# test-board-64.net
KiCad netlist of a schematic drawn in EAGLE
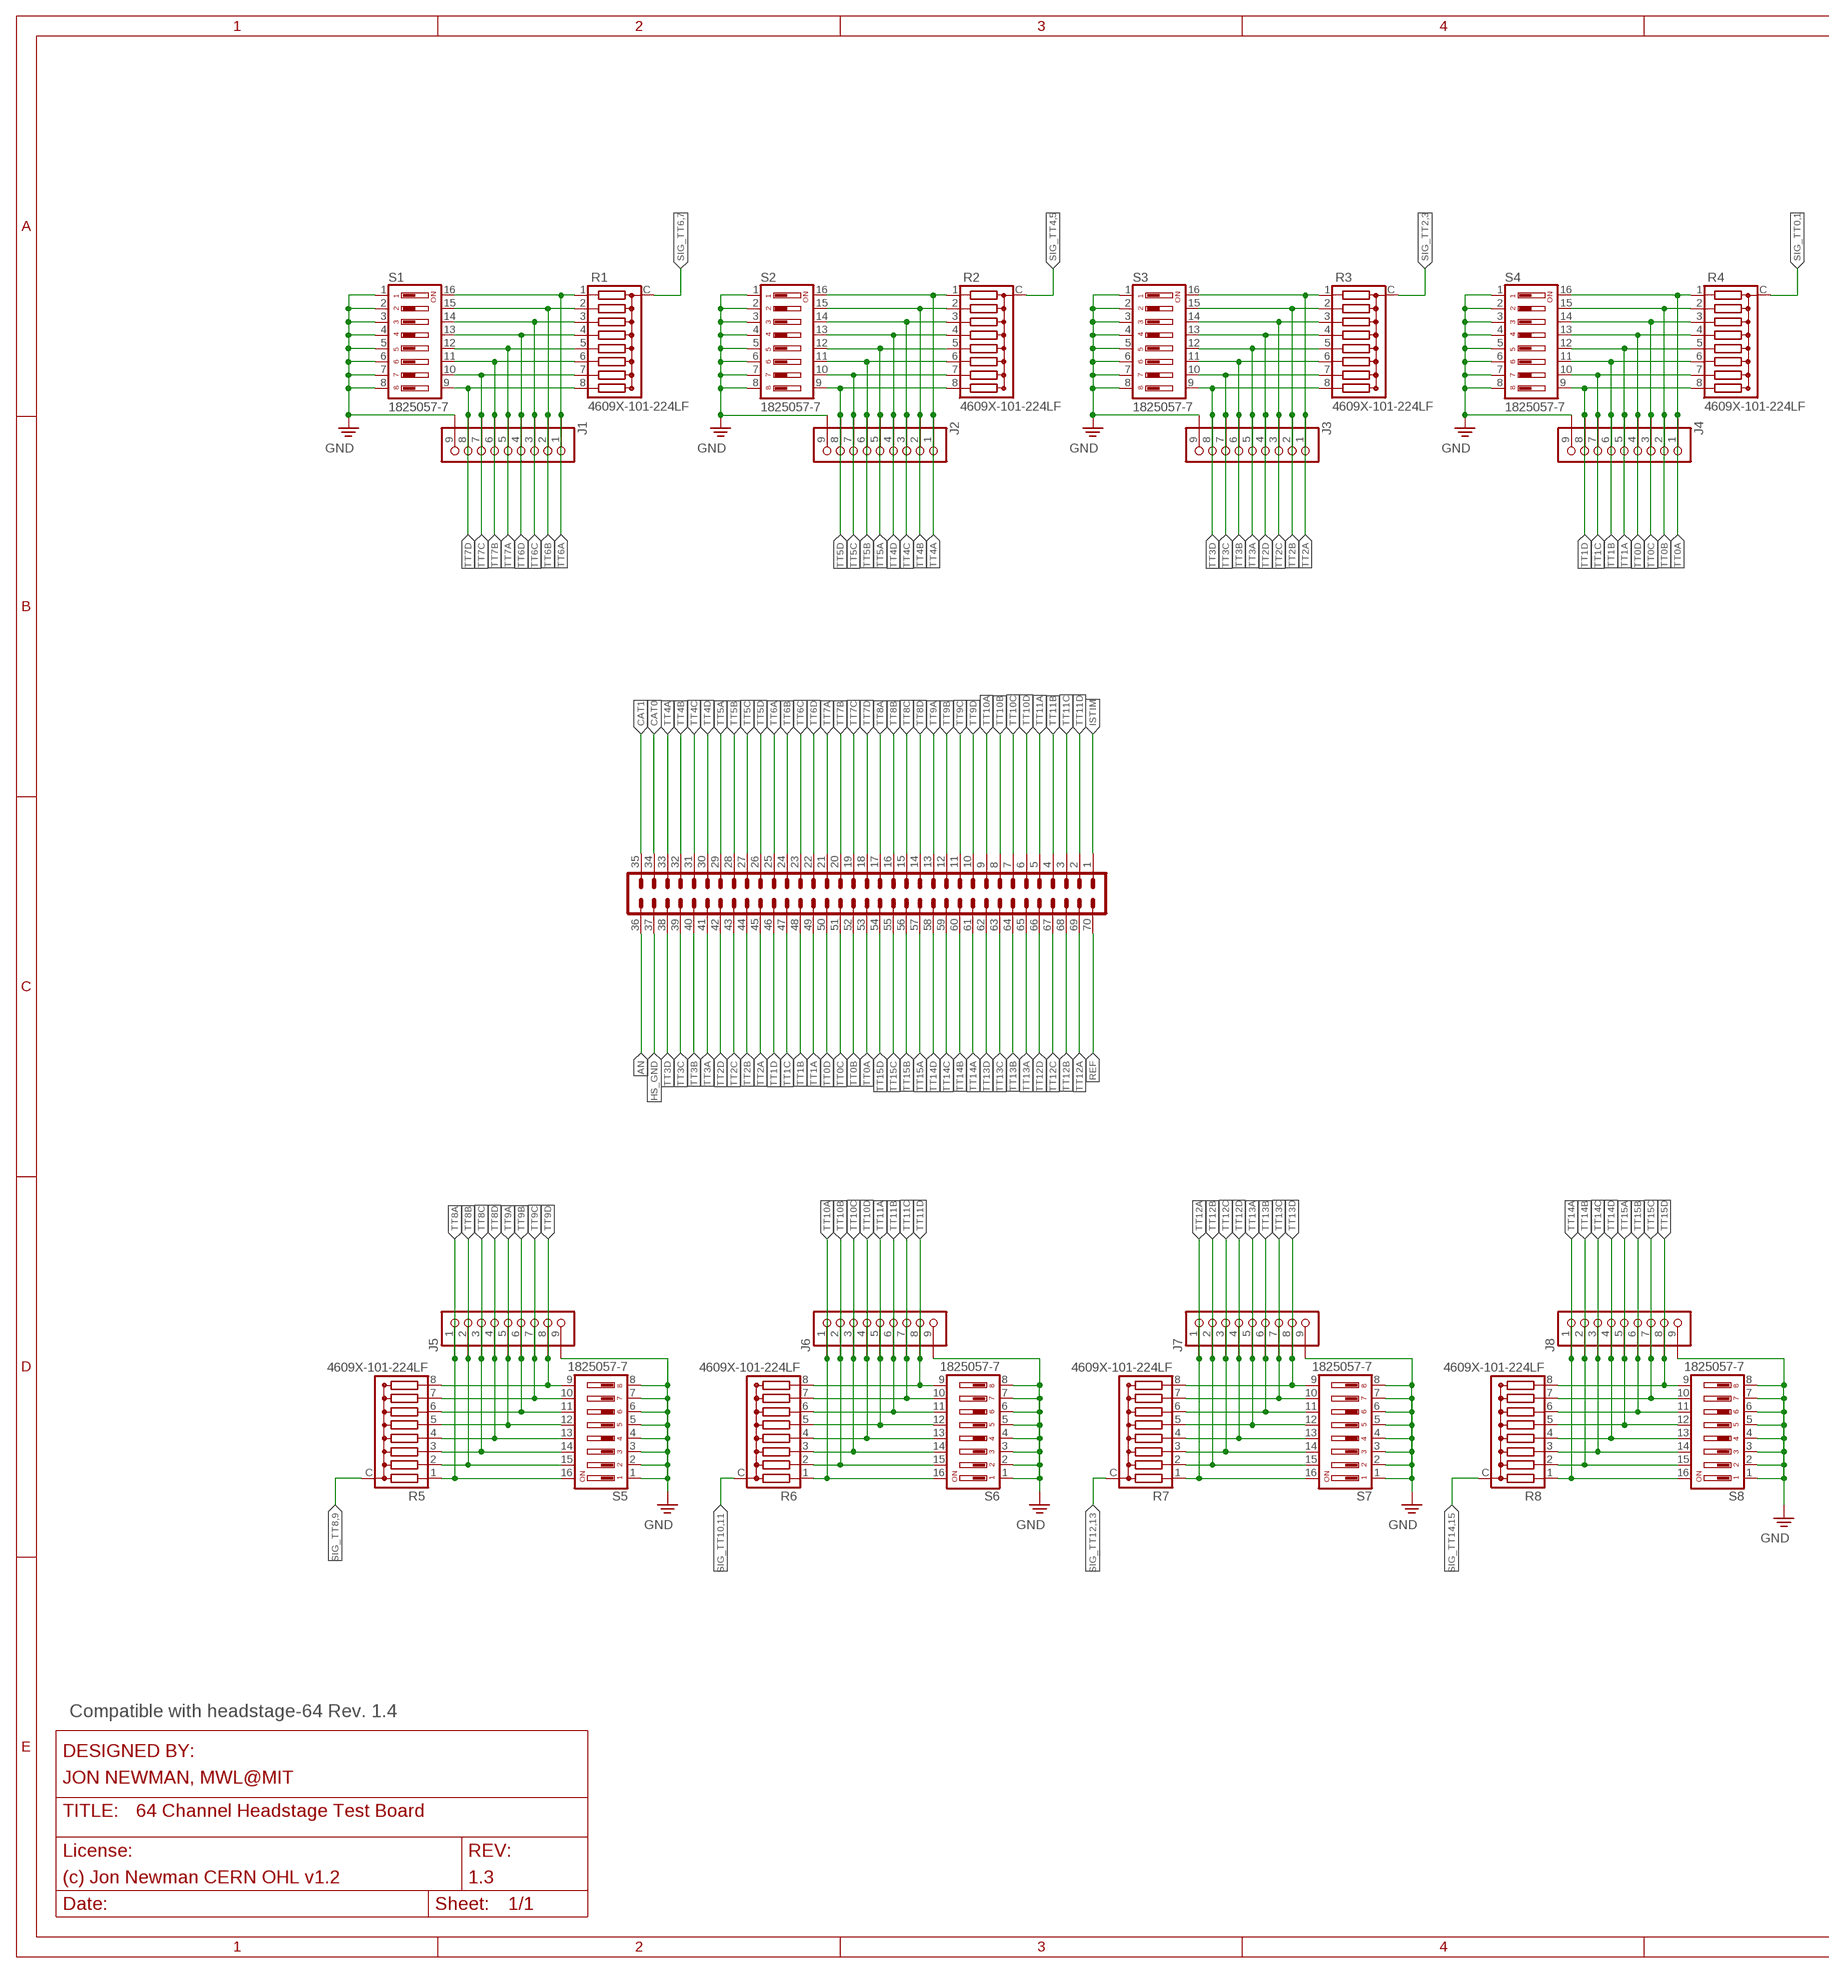
[diagram p0: schematic, sheet 1, part 1 of 2]
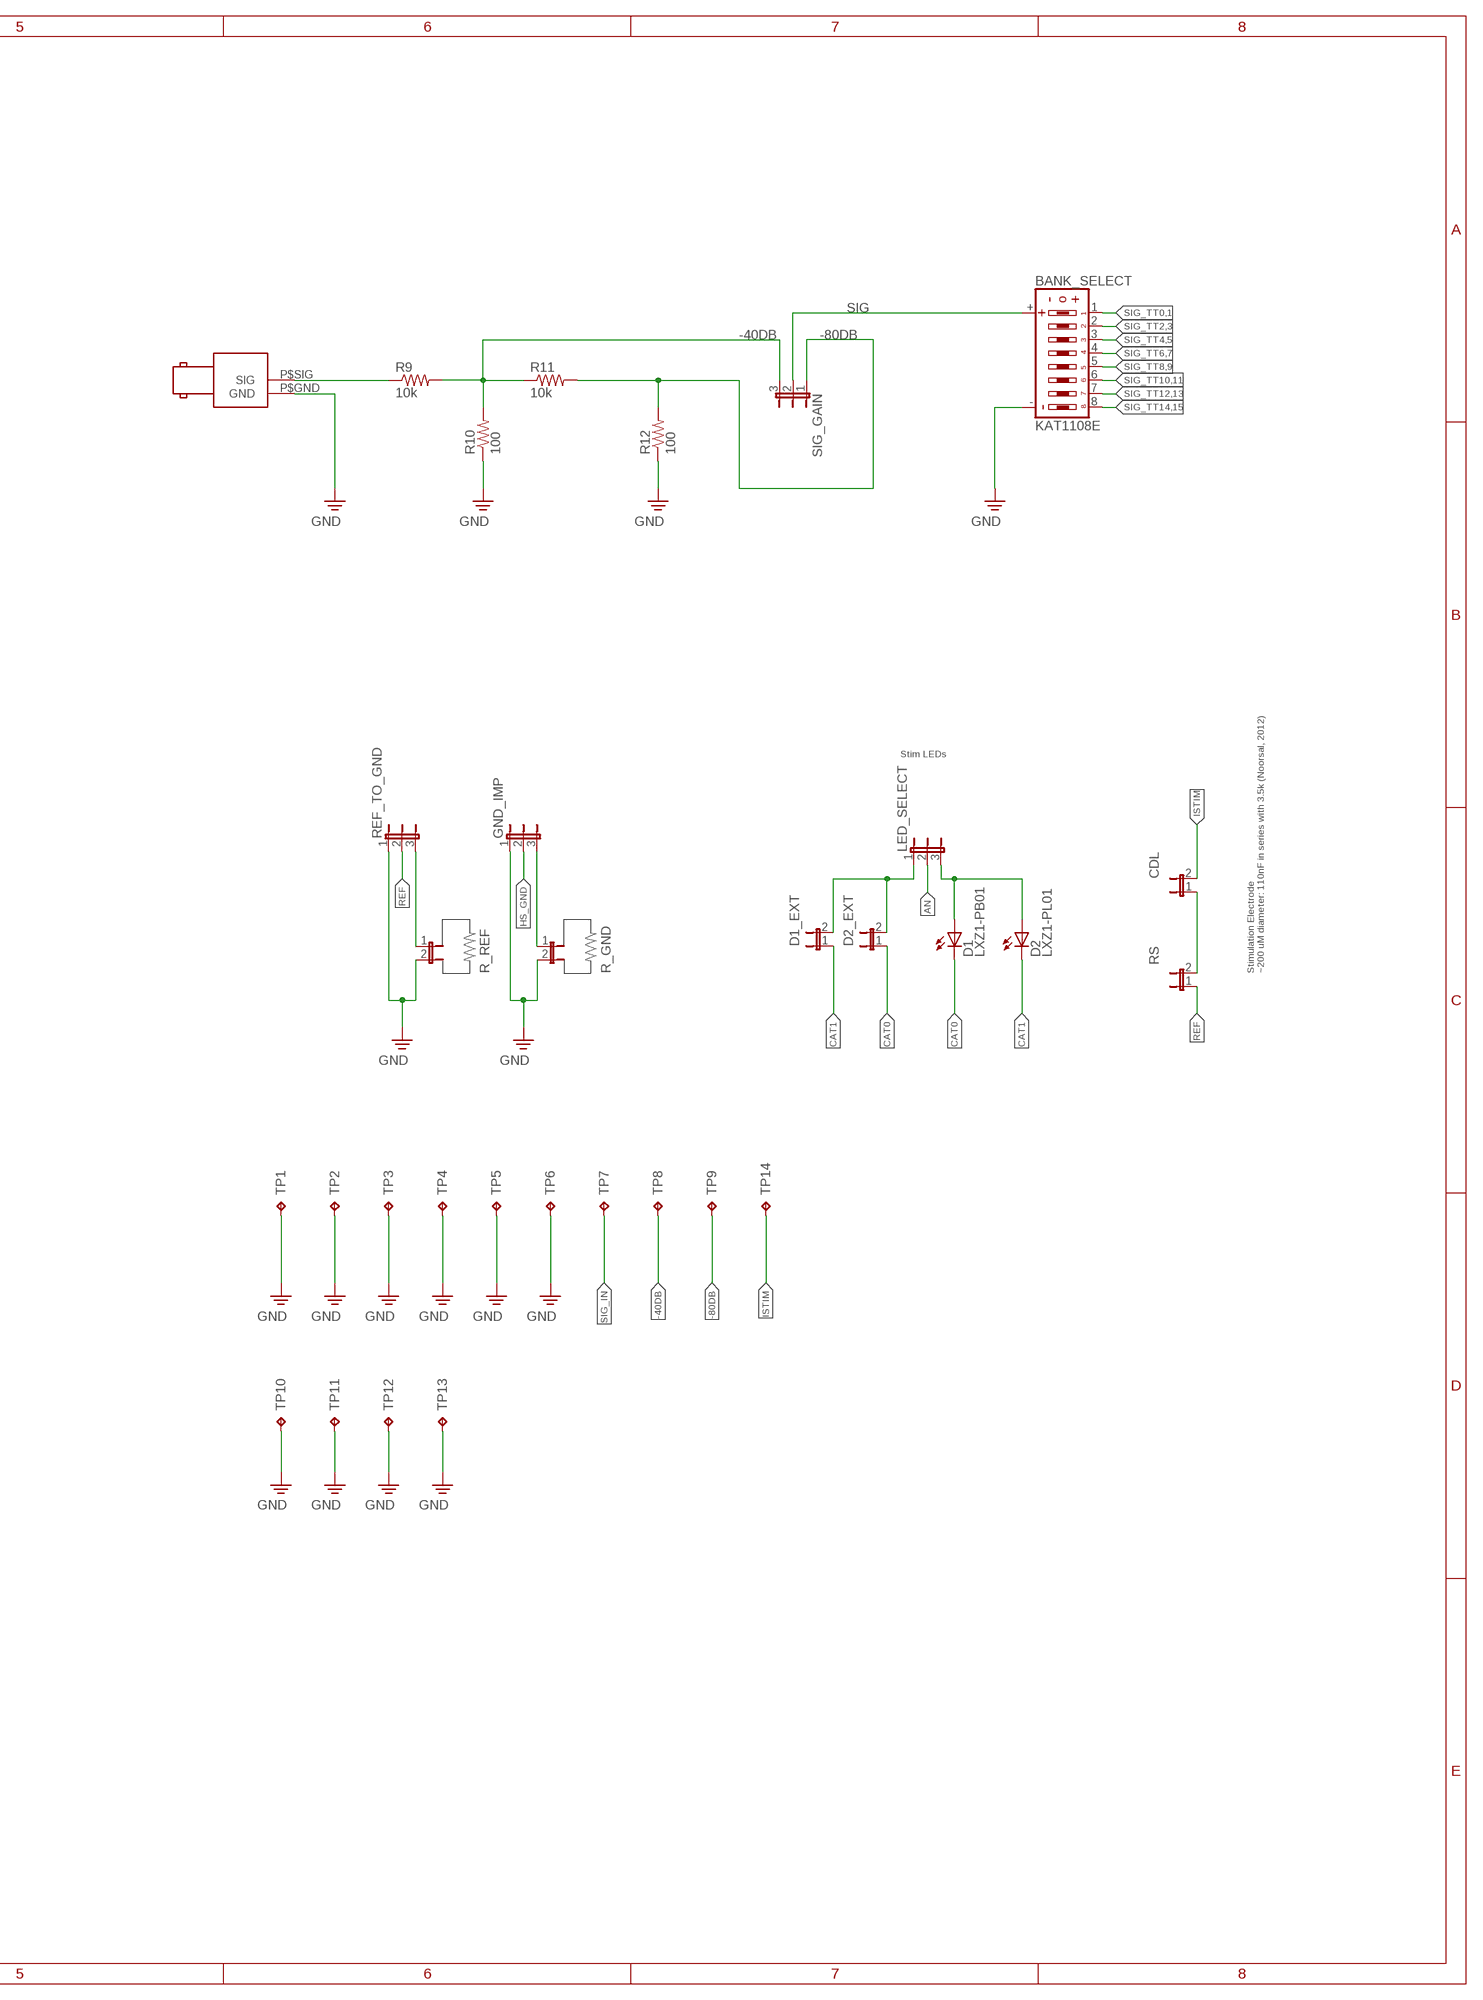
[diagram p1: schematic, sheet 1, part 2 of 2]

(export (version "E")
  (design (tool "Eeschema 10.0.6"))
  (components
    (comp (ref "BANK_SELECT")
      (value "KAT1108E")
      (footprint "eagle-import:206-124_DIP8-SPDT")
      (libsource (lib "eagle-import") (part "DIPSW-008-SPDT_206-124"))
    )
    (comp (ref "CDL")
      (value "SOC2-0.1\"")
      (footprint "eagle-import:JP2")
      (libsource (lib "eagle-import") (part "JP2E_THRU-HOLE"))
    )
    (comp (ref "D1")
      (value "LXZ1-PB01")
      (footprint "eagle-import:LXZ1")
      (libsource (lib "eagle-import") (part "LED_LXZ1"))
    )
    (comp (ref "D1_EXT")
      (value "SOC2-0.1\"")
      (footprint "eagle-import:JP2")
      (libsource (lib "eagle-import") (part "JP2E_THRU-HOLE"))
    )
    (comp (ref "D2")
      (value "LXZ1-PL01")
      (footprint "eagle-import:LXZ1")
      (libsource (lib "eagle-import") (part "LED_LXZ1"))
    )
    (comp (ref "D2_EXT")
      (value "SOC2-0.1\"")
      (footprint "eagle-import:JP2")
      (libsource (lib "eagle-import") (part "JP2E_THRU-HOLE"))
    )
    (comp (ref "GND_IMP")
      (value "JP3-0.1\"")
      (footprint "eagle-import:JP3")
      (libsource (lib "eagle-import") (part "JP3E"))
    )
    (comp (ref "HEADSTAGE")
      (value "DF40C-70DP-0.4V(51)")
      (footprint "eagle-import:DDF40-70REC-LRG")
      (libsource (lib "eagle-import") (part "PINHD-2X35_DF40REF-LRG"))
    )
    (comp (ref "J1")
      (value "PINHD-1X9")
      (footprint "eagle-import:1X09")
      (libsource (lib "eagle-import") (part "PINHD-1X9"))
    )
    (comp (ref "J2")
      (value "PINHD-1X9")
      (footprint "eagle-import:1X09")
      (libsource (lib "eagle-import") (part "PINHD-1X9"))
    )
    (comp (ref "J3")
      (value "PINHD-1X9")
      (footprint "eagle-import:1X09")
      (libsource (lib "eagle-import") (part "PINHD-1X9"))
    )
    (comp (ref "J4")
      (value "PINHD-1X9")
      (footprint "eagle-import:1X09")
      (libsource (lib "eagle-import") (part "PINHD-1X9"))
    )
    (comp (ref "J5")
      (value "PINHD-1X9")
      (footprint "eagle-import:1X09")
      (libsource (lib "eagle-import") (part "PINHD-1X9"))
    )
    (comp (ref "J6")
      (value "PINHD-1X9")
      (footprint "eagle-import:1X09")
      (libsource (lib "eagle-import") (part "PINHD-1X9"))
    )
    (comp (ref "J7")
      (value "PINHD-1X9")
      (footprint "eagle-import:1X09")
      (libsource (lib "eagle-import") (part "PINHD-1X9"))
    )
    (comp (ref "J8")
      (value "PINHD-1X9")
      (footprint "eagle-import:1X09")
      (libsource (lib "eagle-import") (part "PINHD-1X9"))
    )
    (comp (ref "LED_SELECT")
      (value "JP3-0.1\"")
      (footprint "eagle-import:JP3")
      (libsource (lib "eagle-import") (part "JP3E"))
    )
    (comp (ref "R1")
      (value "4609X-101-224LF")
      (footprint "eagle-import:RNX8-0.1")
      (libsource (lib "eagle-import") (part "RN1X8"))
    )
    (comp (ref "R2")
      (value "4609X-101-224LF")
      (footprint "eagle-import:RNX8-0.1")
      (libsource (lib "eagle-import") (part "RN1X8"))
    )
    (comp (ref "R3")
      (value "4609X-101-224LF")
      (footprint "eagle-import:RNX8-0.1")
      (libsource (lib "eagle-import") (part "RN1X8"))
    )
    (comp (ref "R4")
      (value "4609X-101-224LF")
      (footprint "eagle-import:RNX8-0.1")
      (libsource (lib "eagle-import") (part "RN1X8"))
    )
    (comp (ref "R5")
      (value "4609X-101-224LF")
      (footprint "eagle-import:RNX8-0.1")
      (libsource (lib "eagle-import") (part "RN1X8"))
    )
    (comp (ref "R6")
      (value "4609X-101-224LF")
      (footprint "eagle-import:RNX8-0.1")
      (libsource (lib "eagle-import") (part "RN1X8"))
    )
    (comp (ref "R7")
      (value "4609X-101-224LF")
      (footprint "eagle-import:RNX8-0.1")
      (libsource (lib "eagle-import") (part "RN1X8"))
    )
    (comp (ref "R8")
      (value "4609X-101-224LF")
      (footprint "eagle-import:RNX8-0.1")
      (libsource (lib "eagle-import") (part "RN1X8"))
    )
    (comp (ref "R9")
      (value "10k")
      (footprint "eagle-import:0805")
      (libsource (lib "eagle-import") (part "R_0805"))
    )
    (comp (ref "R10")
      (value "100")
      (footprint "eagle-import:0805")
      (libsource (lib "eagle-import") (part "R_0805"))
    )
    (comp (ref "R11")
      (value "10k")
      (footprint "eagle-import:0805")
      (libsource (lib "eagle-import") (part "R_0805"))
    )
    (comp (ref "R12")
      (value "100")
      (footprint "eagle-import:0805")
      (libsource (lib "eagle-import") (part "R_0805"))
    )
    (comp (ref "REF_TO_GND")
      (value "JP3-0.1\"")
      (footprint "eagle-import:JP3")
      (libsource (lib "eagle-import") (part "JP3E"))
    )
    (comp (ref "RS")
      (value "SOC2-0.1\"")
      (footprint "eagle-import:JP2")
      (libsource (lib "eagle-import") (part "JP2E_THRU-HOLE"))
    )
    (comp (ref "R_GND")
      (value "SOC2-0.1\"")
      (footprint "eagle-import:JP2")
      (libsource (lib "eagle-import") (part "JP2E_THRU-HOLE"))
    )
    (comp (ref "R_REF")
      (value "SOC2-0.1\"")
      (footprint "eagle-import:JP2")
      (libsource (lib "eagle-import") (part "JP2E_THRU-HOLE"))
    )
    (comp (ref "S1")
      (value "1825057-7")
      (footprint "eagle-import:ADE_DIP8-SPST")
      (libsource (lib "eagle-import") (part "DIPSW-008_ADE"))
    )
    (comp (ref "S2")
      (value "1825057-7")
      (footprint "eagle-import:ADE_DIP8-SPST")
      (libsource (lib "eagle-import") (part "DIPSW-008_ADE"))
    )
    (comp (ref "S3")
      (value "1825057-7")
      (footprint "eagle-import:ADE_DIP8-SPST")
      (libsource (lib "eagle-import") (part "DIPSW-008_ADE"))
    )
    (comp (ref "S4")
      (value "1825057-7")
      (footprint "eagle-import:ADE_DIP8-SPST")
      (libsource (lib "eagle-import") (part "DIPSW-008_ADE"))
    )
    (comp (ref "S5")
      (value "1825057-7")
      (footprint "eagle-import:ADE_DIP8-SPST")
      (libsource (lib "eagle-import") (part "DIPSW-008_ADE"))
    )
    (comp (ref "S6")
      (value "1825057-7")
      (footprint "eagle-import:ADE_DIP8-SPST")
      (libsource (lib "eagle-import") (part "DIPSW-008_ADE"))
    )
    (comp (ref "S7")
      (value "1825057-7")
      (footprint "eagle-import:ADE_DIP8-SPST")
      (libsource (lib "eagle-import") (part "DIPSW-008_ADE"))
    )
    (comp (ref "S8")
      (value "1825057-7")
      (footprint "eagle-import:ADE_DIP8-SPST")
      (libsource (lib "eagle-import") (part "DIPSW-008_ADE"))
    )
    (comp (ref "SIG_GAIN")
      (value "JP3-0.1\"")
      (footprint "eagle-import:JP3")
      (libsource (lib "eagle-import") (part "JP3E"))
    )
    (comp (ref "SIG_IN")
      (value "1-1634622-0")
      (footprint "eagle-import:BNC_RIGHT_ANGLE")
      (libsource (lib "eagle-import") (part "BNC_RIGHT_ANGLE"))
    )
    (comp (ref "TP1")
      (value "GND")
      (footprint "eagle-import:P1-20")
      (libsource (lib "eagle-import") (part "TPPAD1-20"))
    )
    (comp (ref "TP2")
      (value "GND")
      (footprint "eagle-import:P1-20")
      (libsource (lib "eagle-import") (part "TPPAD1-20"))
    )
    (comp (ref "TP3")
      (value "GND")
      (footprint "eagle-import:P1-20")
      (libsource (lib "eagle-import") (part "TPPAD1-20"))
    )
    (comp (ref "TP4")
      (value "GND")
      (footprint "eagle-import:P1-20")
      (libsource (lib "eagle-import") (part "TPPAD1-20"))
    )
    (comp (ref "TP5")
      (value "GND")
      (footprint "eagle-import:P1-20")
      (libsource (lib "eagle-import") (part "TPPAD1-20"))
    )
    (comp (ref "TP6")
      (value "GND")
      (footprint "eagle-import:P1-20")
      (libsource (lib "eagle-import") (part "TPPAD1-20"))
    )
    (comp (ref "TP7")
      (value "SIG_IN")
      (footprint "eagle-import:P1-20")
      (libsource (lib "eagle-import") (part "TPPAD1-20"))
    )
    (comp (ref "TP8")
      (value "-40dB")
      (footprint "eagle-import:P1-20")
      (libsource (lib "eagle-import") (part "TPPAD1-20"))
    )
    (comp (ref "TP9")
      (value "-80dB")
      (footprint "eagle-import:P1-20")
      (libsource (lib "eagle-import") (part "TPPAD1-20"))
    )
    (comp (ref "TP10")
      (value "TP_4-40")
      (footprint "eagle-import:4-40_PLATED")
      (libsource (lib "eagle-import") (part "TP_4-40"))
    )
    (comp (ref "TP11")
      (value "TP_4-40")
      (footprint "eagle-import:4-40_PLATED")
      (libsource (lib "eagle-import") (part "TP_4-40"))
    )
    (comp (ref "TP12")
      (value "TP_4-40")
      (footprint "eagle-import:4-40_PLATED")
      (libsource (lib "eagle-import") (part "TP_4-40"))
    )
    (comp (ref "TP13")
      (value "TP_4-40")
      (footprint "eagle-import:4-40_PLATED")
      (libsource (lib "eagle-import") (part "TP_4-40"))
    )
    (comp (ref "TP14")
      (value "V_ESTIM")
      (footprint "eagle-import:P1-20")
      (libsource (lib "eagle-import") (part "TPPAD1-20"))
    )
  )
  (nets
    (net (code "1") (name "-40DB") (class "Default")
      (node (ref "R10") (pin "2") (pinfunction "2_2") (pintype "passive"))
      (node (ref "R11") (pin "1") (pinfunction "1_1") (pintype "passive"))
      (node (ref "R9") (pin "2") (pinfunction "2_2") (pintype "passive"))
      (node (ref "SIG_GAIN") (pin "3") (pinfunction "3_3") (pintype "passive"))
      (node (ref "TP8") (pin "TP") (pinfunction "TP_TP") (pintype "input"))
    )
    (net (code "2") (name "-80DB") (class "Default")
      (node (ref "R11") (pin "2") (pinfunction "2_2") (pintype "passive"))
      (node (ref "R12") (pin "2") (pinfunction "2_2") (pintype "passive"))
      (node (ref "SIG_GAIN") (pin "1") (pinfunction "1_1") (pintype "passive"))
      (node (ref "TP9") (pin "TP") (pinfunction "TP_TP") (pintype "input"))
    )
    (net (code "3") (name "/SIG") (class "Default")
      (node (ref "BANK_SELECT") (pin "+") (pinfunction "+_+") (pintype "passive"))
      (node (ref "SIG_GAIN") (pin "2") (pinfunction "2_2") (pintype "passive"))
    )
    (net (code "4") (name "AN") (class "Default")
      (node (ref "HEADSTAGE") (pin "36") (pinfunction "36_36") (pintype "bidirectional"))
      (node (ref "LED_SELECT") (pin "2") (pinfunction "2_2") (pintype "passive"))
    )
    (net (code "5") (name "CAT0") (class "Default")
      (node (ref "D1") (pin "C") (pinfunction "C_C") (pintype "passive"))
      (node (ref "D2_EXT") (pin "1") (pinfunction "1_1") (pintype "passive"))
      (node (ref "HEADSTAGE") (pin "34") (pinfunction "34_34") (pintype "bidirectional"))
    )
    (net (code "6") (name "CAT1") (class "Default")
      (node (ref "D1_EXT") (pin "1") (pinfunction "1_1") (pintype "passive"))
      (node (ref "D2") (pin "C") (pinfunction "C_C") (pintype "passive"))
      (node (ref "HEADSTAGE") (pin "35") (pinfunction "35_35") (pintype "bidirectional"))
    )
    (net (code "7") (name "GND") (class "Default")
      (node (ref "BANK_SELECT") (pin "-") (pinfunction "-_-") (pintype "passive"))
      (node (ref "GND_IMP") (pin "1") (pinfunction "1_1") (pintype "passive"))
      (node (ref "J1") (pin "9") (pinfunction "9_9") (pintype "passive"))
      (node (ref "J2") (pin "9") (pinfunction "9_9") (pintype "passive"))
      (node (ref "J3") (pin "9") (pinfunction "9_9") (pintype "passive"))
      (node (ref "J4") (pin "9") (pinfunction "9_9") (pintype "passive"))
      (node (ref "J5") (pin "9") (pinfunction "9_9") (pintype "passive"))
      (node (ref "J6") (pin "9") (pinfunction "9_9") (pintype "passive"))
      (node (ref "J7") (pin "9") (pinfunction "9_9") (pintype "passive"))
      (node (ref "J8") (pin "9") (pinfunction "9_9") (pintype "passive"))
      (node (ref "R10") (pin "1") (pinfunction "1_1") (pintype "passive"))
      (node (ref "R12") (pin "1") (pinfunction "1_1") (pintype "passive"))
      (node (ref "REF_TO_GND") (pin "1") (pinfunction "1_1") (pintype "passive"))
      (node (ref "R_GND") (pin "2") (pinfunction "2_2") (pintype "passive"))
      (node (ref "R_REF") (pin "2") (pinfunction "2_2") (pintype "passive"))
      (node (ref "S1") (pin "1") (pinfunction "1_1") (pintype "passive"))
      (node (ref "S1") (pin "2") (pinfunction "2_2") (pintype "passive"))
      (node (ref "S1") (pin "3") (pinfunction "3_3") (pintype "passive"))
      (node (ref "S1") (pin "4") (pinfunction "4_4") (pintype "passive"))
      (node (ref "S1") (pin "5") (pinfunction "5_5") (pintype "passive"))
      (node (ref "S1") (pin "6") (pinfunction "6_6") (pintype "passive"))
      (node (ref "S1") (pin "7") (pinfunction "7_7") (pintype "passive"))
      (node (ref "S1") (pin "8") (pinfunction "8_8") (pintype "passive"))
      (node (ref "S2") (pin "1") (pinfunction "1_1") (pintype "passive"))
      (node (ref "S2") (pin "2") (pinfunction "2_2") (pintype "passive"))
      (node (ref "S2") (pin "3") (pinfunction "3_3") (pintype "passive"))
      (node (ref "S2") (pin "4") (pinfunction "4_4") (pintype "passive"))
      (node (ref "S2") (pin "5") (pinfunction "5_5") (pintype "passive"))
      (node (ref "S2") (pin "6") (pinfunction "6_6") (pintype "passive"))
      (node (ref "S2") (pin "7") (pinfunction "7_7") (pintype "passive"))
      (node (ref "S2") (pin "8") (pinfunction "8_8") (pintype "passive"))
      (node (ref "S3") (pin "1") (pinfunction "1_1") (pintype "passive"))
      (node (ref "S3") (pin "2") (pinfunction "2_2") (pintype "passive"))
      (node (ref "S3") (pin "3") (pinfunction "3_3") (pintype "passive"))
      (node (ref "S3") (pin "4") (pinfunction "4_4") (pintype "passive"))
      (node (ref "S3") (pin "5") (pinfunction "5_5") (pintype "passive"))
      (node (ref "S3") (pin "6") (pinfunction "6_6") (pintype "passive"))
      (node (ref "S3") (pin "7") (pinfunction "7_7") (pintype "passive"))
      (node (ref "S3") (pin "8") (pinfunction "8_8") (pintype "passive"))
      (node (ref "S4") (pin "1") (pinfunction "1_1") (pintype "passive"))
      (node (ref "S4") (pin "2") (pinfunction "2_2") (pintype "passive"))
      (node (ref "S4") (pin "3") (pinfunction "3_3") (pintype "passive"))
      (node (ref "S4") (pin "4") (pinfunction "4_4") (pintype "passive"))
      (node (ref "S4") (pin "5") (pinfunction "5_5") (pintype "passive"))
      (node (ref "S4") (pin "6") (pinfunction "6_6") (pintype "passive"))
      (node (ref "S4") (pin "7") (pinfunction "7_7") (pintype "passive"))
      (node (ref "S4") (pin "8") (pinfunction "8_8") (pintype "passive"))
      (node (ref "S5") (pin "1") (pinfunction "1_1") (pintype "passive"))
      (node (ref "S5") (pin "2") (pinfunction "2_2") (pintype "passive"))
      (node (ref "S5") (pin "3") (pinfunction "3_3") (pintype "passive"))
      (node (ref "S5") (pin "4") (pinfunction "4_4") (pintype "passive"))
      (node (ref "S5") (pin "5") (pinfunction "5_5") (pintype "passive"))
      (node (ref "S5") (pin "6") (pinfunction "6_6") (pintype "passive"))
      (node (ref "S5") (pin "7") (pinfunction "7_7") (pintype "passive"))
      (node (ref "S5") (pin "8") (pinfunction "8_8") (pintype "passive"))
      (node (ref "S6") (pin "1") (pinfunction "1_1") (pintype "passive"))
      (node (ref "S6") (pin "2") (pinfunction "2_2") (pintype "passive"))
      (node (ref "S6") (pin "3") (pinfunction "3_3") (pintype "passive"))
      (node (ref "S6") (pin "4") (pinfunction "4_4") (pintype "passive"))
      (node (ref "S6") (pin "5") (pinfunction "5_5") (pintype "passive"))
      (node (ref "S6") (pin "6") (pinfunction "6_6") (pintype "passive"))
      (node (ref "S6") (pin "7") (pinfunction "7_7") (pintype "passive"))
      (node (ref "S6") (pin "8") (pinfunction "8_8") (pintype "passive"))
      (node (ref "S7") (pin "1") (pinfunction "1_1") (pintype "passive"))
      (node (ref "S7") (pin "2") (pinfunction "2_2") (pintype "passive"))
      (node (ref "S7") (pin "3") (pinfunction "3_3") (pintype "passive"))
      (node (ref "S7") (pin "4") (pinfunction "4_4") (pintype "passive"))
      (node (ref "S7") (pin "5") (pinfunction "5_5") (pintype "passive"))
      (node (ref "S7") (pin "6") (pinfunction "6_6") (pintype "passive"))
      (node (ref "S7") (pin "7") (pinfunction "7_7") (pintype "passive"))
      (node (ref "S7") (pin "8") (pinfunction "8_8") (pintype "passive"))
      (node (ref "S8") (pin "1") (pinfunction "1_1") (pintype "passive"))
      (node (ref "S8") (pin "2") (pinfunction "2_2") (pintype "passive"))
      (node (ref "S8") (pin "3") (pinfunction "3_3") (pintype "passive"))
      (node (ref "S8") (pin "4") (pinfunction "4_4") (pintype "passive"))
      (node (ref "S8") (pin "5") (pinfunction "5_5") (pintype "passive"))
      (node (ref "S8") (pin "6") (pinfunction "6_6") (pintype "passive"))
      (node (ref "S8") (pin "7") (pinfunction "7_7") (pintype "passive"))
      (node (ref "S8") (pin "8") (pinfunction "8_8") (pintype "passive"))
      (node (ref "SIG_IN") (pin "P$GND") (pinfunction "GND_P$GND") (pintype "bidirectional"))
      (node (ref "TP1") (pin "TP") (pinfunction "TP_TP") (pintype "input"))
      (node (ref "TP10") (pin "P$1") (pinfunction "TP_P$1") (pintype "input"))
      (node (ref "TP11") (pin "P$1") (pinfunction "TP_P$1") (pintype "input"))
      (node (ref "TP12") (pin "P$1") (pinfunction "TP_P$1") (pintype "input"))
      (node (ref "TP13") (pin "P$1") (pinfunction "TP_P$1") (pintype "input"))
      (node (ref "TP2") (pin "TP") (pinfunction "TP_TP") (pintype "input"))
      (node (ref "TP3") (pin "TP") (pinfunction "TP_TP") (pintype "input"))
      (node (ref "TP4") (pin "TP") (pinfunction "TP_TP") (pintype "input"))
      (node (ref "TP5") (pin "TP") (pinfunction "TP_TP") (pintype "input"))
      (node (ref "TP6") (pin "TP") (pinfunction "TP_TP") (pintype "input"))
    )
    (net (code "8") (name "HS_GND") (class "Default")
      (node (ref "GND_IMP") (pin "2") (pinfunction "2_2") (pintype "passive"))
      (node (ref "HEADSTAGE") (pin "37") (pinfunction "37_37") (pintype "bidirectional"))
    )
    (net (code "9") (name "ISTIM") (class "Default")
      (node (ref "CDL") (pin "2") (pinfunction "2_2") (pintype "passive"))
      (node (ref "HEADSTAGE") (pin "1") (pinfunction "1_1") (pintype "bidirectional"))
      (node (ref "TP14") (pin "TP") (pinfunction "TP_TP") (pintype "input"))
    )
    (net (code "10") (name "Net-(CDL-Pad1)") (class "Default")
      (node (ref "CDL") (pin "1") (pinfunction "1_1") (pintype "passive"))
      (node (ref "RS") (pin "2") (pinfunction "2_2") (pintype "passive"))
    )
    (net (code "11") (name "Net-(D1-PadA)") (class "Default")
      (node (ref "D1") (pin "A") (pinfunction "A_A") (pintype "passive"))
      (node (ref "D2") (pin "A") (pinfunction "A_A") (pintype "passive"))
      (node (ref "LED_SELECT") (pin "3") (pinfunction "3_3") (pintype "passive"))
    )
    (net (code "12") (name "Net-(D1_EXT-Pad2)") (class "Default")
      (node (ref "D1_EXT") (pin "2") (pinfunction "2_2") (pintype "passive"))
      (node (ref "D2_EXT") (pin "2") (pinfunction "2_2") (pintype "passive"))
      (node (ref "LED_SELECT") (pin "1") (pinfunction "1_1") (pintype "passive"))
    )
    (net (code "13") (name "Net-(GND_IMP-Pad3)") (class "Default")
      (node (ref "GND_IMP") (pin "3") (pinfunction "3_3") (pintype "passive"))
      (node (ref "R_GND") (pin "1") (pinfunction "1_1") (pintype "passive"))
    )
    (net (code "14") (name "Net-(REF_TO_GND-Pad3)") (class "Default")
      (node (ref "REF_TO_GND") (pin "3") (pinfunction "3_3") (pintype "passive"))
      (node (ref "R_REF") (pin "1") (pinfunction "1_1") (pintype "passive"))
    )
    (net (code "15") (name "REF") (class "Default")
      (node (ref "HEADSTAGE") (pin "70") (pinfunction "70_70") (pintype "bidirectional"))
      (node (ref "REF_TO_GND") (pin "2") (pinfunction "2_2") (pintype "passive"))
      (node (ref "RS") (pin "1") (pinfunction "1_1") (pintype "passive"))
    )
    (net (code "16") (name "SIG_IN") (class "Default")
      (node (ref "R9") (pin "1") (pinfunction "1_1") (pintype "passive"))
      (node (ref "SIG_IN") (pin "P$SIG") (pinfunction "SIG_P$SIG") (pintype "bidirectional"))
      (node (ref "TP7") (pin "TP") (pinfunction "TP_TP") (pintype "input"))
    )
    (net (code "17") (name "SIG_TT0,1") (class "Default")
      (node (ref "BANK_SELECT") (pin "1") (pinfunction "1_1") (pintype "passive"))
      (node (ref "R4") (pin "C") (pinfunction "C_C") (pintype "passive"))
    )
    (net (code "18") (name "SIG_TT2,3") (class "Default")
      (node (ref "BANK_SELECT") (pin "2") (pinfunction "2_2") (pintype "passive"))
      (node (ref "R3") (pin "C") (pinfunction "C_C") (pintype "passive"))
    )
    (net (code "19") (name "SIG_TT4,5") (class "Default")
      (node (ref "BANK_SELECT") (pin "3") (pinfunction "3_3") (pintype "passive"))
      (node (ref "R2") (pin "C") (pinfunction "C_C") (pintype "passive"))
    )
    (net (code "20") (name "SIG_TT6,7") (class "Default")
      (node (ref "BANK_SELECT") (pin "4") (pinfunction "4_4") (pintype "passive"))
      (node (ref "R1") (pin "C") (pinfunction "C_C") (pintype "passive"))
    )
    (net (code "21") (name "SIG_TT8,9") (class "Default")
      (node (ref "BANK_SELECT") (pin "5") (pinfunction "5_5") (pintype "passive"))
      (node (ref "R5") (pin "C") (pinfunction "C_C") (pintype "passive"))
    )
    (net (code "22") (name "SIG_TT10,11") (class "Default")
      (node (ref "BANK_SELECT") (pin "6") (pinfunction "6_6") (pintype "passive"))
      (node (ref "R6") (pin "C") (pinfunction "C_C") (pintype "passive"))
    )
    (net (code "23") (name "SIG_TT12,13") (class "Default")
      (node (ref "BANK_SELECT") (pin "7") (pinfunction "7_7") (pintype "passive"))
      (node (ref "R7") (pin "C") (pinfunction "C_C") (pintype "passive"))
    )
    (net (code "24") (name "SIG_TT14,15") (class "Default")
      (node (ref "BANK_SELECT") (pin "8") (pinfunction "8_8") (pintype "passive"))
      (node (ref "R8") (pin "C") (pinfunction "C_C") (pintype "passive"))
    )
    (net (code "25") (name "TT0A") (class "Default")
      (node (ref "HEADSTAGE") (pin "53") (pinfunction "53_53") (pintype "bidirectional"))
      (node (ref "J4") (pin "1") (pinfunction "1_1") (pintype "passive"))
      (node (ref "R4") (pin "1") (pinfunction "1_1") (pintype "passive"))
      (node (ref "S4") (pin "16") (pinfunction "16_16") (pintype "passive"))
    )
    (net (code "26") (name "TT0B") (class "Default")
      (node (ref "HEADSTAGE") (pin "52") (pinfunction "52_52") (pintype "bidirectional"))
      (node (ref "J4") (pin "2") (pinfunction "2_2") (pintype "passive"))
      (node (ref "R4") (pin "2") (pinfunction "2_2") (pintype "passive"))
      (node (ref "S4") (pin "15") (pinfunction "15_15") (pintype "passive"))
    )
    (net (code "27") (name "TT0C") (class "Default")
      (node (ref "HEADSTAGE") (pin "51") (pinfunction "51_51") (pintype "bidirectional"))
      (node (ref "J4") (pin "3") (pinfunction "3_3") (pintype "passive"))
      (node (ref "R4") (pin "3") (pinfunction "3_3") (pintype "passive"))
      (node (ref "S4") (pin "14") (pinfunction "14_14") (pintype "passive"))
    )
    (net (code "28") (name "TT0D") (class "Default")
      (node (ref "HEADSTAGE") (pin "50") (pinfunction "50_50") (pintype "bidirectional"))
      (node (ref "J4") (pin "4") (pinfunction "4_4") (pintype "passive"))
      (node (ref "R4") (pin "4") (pinfunction "4_4") (pintype "passive"))
      (node (ref "S4") (pin "13") (pinfunction "13_13") (pintype "passive"))
    )
    (net (code "29") (name "TT1A") (class "Default")
      (node (ref "HEADSTAGE") (pin "49") (pinfunction "49_49") (pintype "bidirectional"))
      (node (ref "J4") (pin "5") (pinfunction "5_5") (pintype "passive"))
      (node (ref "R4") (pin "5") (pinfunction "5_5") (pintype "passive"))
      (node (ref "S4") (pin "12") (pinfunction "12_12") (pintype "passive"))
    )
    (net (code "30") (name "TT1B") (class "Default")
      (node (ref "HEADSTAGE") (pin "48") (pinfunction "48_48") (pintype "bidirectional"))
      (node (ref "J4") (pin "6") (pinfunction "6_6") (pintype "passive"))
      (node (ref "R4") (pin "6") (pinfunction "6_6") (pintype "passive"))
      (node (ref "S4") (pin "11") (pinfunction "11_11") (pintype "passive"))
    )
    (net (code "31") (name "TT1C") (class "Default")
      (node (ref "HEADSTAGE") (pin "47") (pinfunction "47_47") (pintype "bidirectional"))
      (node (ref "J4") (pin "7") (pinfunction "7_7") (pintype "passive"))
      (node (ref "R4") (pin "7") (pinfunction "7_7") (pintype "passive"))
      (node (ref "S4") (pin "10") (pinfunction "10_10") (pintype "passive"))
    )
    (net (code "32") (name "TT1D") (class "Default")
      (node (ref "HEADSTAGE") (pin "46") (pinfunction "46_46") (pintype "bidirectional"))
      (node (ref "J4") (pin "8") (pinfunction "8_8") (pintype "passive"))
      (node (ref "R4") (pin "8") (pinfunction "8_8") (pintype "passive"))
      (node (ref "S4") (pin "9") (pinfunction "9_9") (pintype "passive"))
    )
    (net (code "33") (name "TT2A") (class "Default")
      (node (ref "HEADSTAGE") (pin "45") (pinfunction "45_45") (pintype "bidirectional"))
      (node (ref "J3") (pin "1") (pinfunction "1_1") (pintype "passive"))
      (node (ref "R3") (pin "1") (pinfunction "1_1") (pintype "passive"))
      (node (ref "S3") (pin "16") (pinfunction "16_16") (pintype "passive"))
    )
    (net (code "34") (name "TT2B") (class "Default")
      (node (ref "HEADSTAGE") (pin "44") (pinfunction "44_44") (pintype "bidirectional"))
      (node (ref "J3") (pin "2") (pinfunction "2_2") (pintype "passive"))
      (node (ref "R3") (pin "2") (pinfunction "2_2") (pintype "passive"))
      (node (ref "S3") (pin "15") (pinfunction "15_15") (pintype "passive"))
    )
    (net (code "35") (name "TT2C") (class "Default")
      (node (ref "HEADSTAGE") (pin "43") (pinfunction "43_43") (pintype "bidirectional"))
      (node (ref "J3") (pin "3") (pinfunction "3_3") (pintype "passive"))
      (node (ref "R3") (pin "3") (pinfunction "3_3") (pintype "passive"))
      (node (ref "S3") (pin "14") (pinfunction "14_14") (pintype "passive"))
    )
    (net (code "36") (name "TT2D") (class "Default")
      (node (ref "HEADSTAGE") (pin "42") (pinfunction "42_42") (pintype "bidirectional"))
      (node (ref "J3") (pin "4") (pinfunction "4_4") (pintype "passive"))
      (node (ref "R3") (pin "4") (pinfunction "4_4") (pintype "passive"))
      (node (ref "S3") (pin "13") (pinfunction "13_13") (pintype "passive"))
    )
    (net (code "37") (name "TT3A") (class "Default")
      (node (ref "HEADSTAGE") (pin "41") (pinfunction "41_41") (pintype "bidirectional"))
      (node (ref "J3") (pin "5") (pinfunction "5_5") (pintype "passive"))
      (node (ref "R3") (pin "5") (pinfunction "5_5") (pintype "passive"))
      (node (ref "S3") (pin "12") (pinfunction "12_12") (pintype "passive"))
    )
    (net (code "38") (name "TT3B") (class "Default")
      (node (ref "HEADSTAGE") (pin "40") (pinfunction "40_40") (pintype "bidirectional"))
      (node (ref "J3") (pin "6") (pinfunction "6_6") (pintype "passive"))
      (node (ref "R3") (pin "6") (pinfunction "6_6") (pintype "passive"))
      (node (ref "S3") (pin "11") (pinfunction "11_11") (pintype "passive"))
    )
    (net (code "39") (name "TT3C") (class "Default")
      (node (ref "HEADSTAGE") (pin "39") (pinfunction "39_39") (pintype "bidirectional"))
      (node (ref "J3") (pin "7") (pinfunction "7_7") (pintype "passive"))
      (node (ref "R3") (pin "7") (pinfunction "7_7") (pintype "passive"))
      (node (ref "S3") (pin "10") (pinfunction "10_10") (pintype "passive"))
    )
    (net (code "40") (name "TT3D") (class "Default")
      (node (ref "HEADSTAGE") (pin "38") (pinfunction "38_38") (pintype "bidirectional"))
      (node (ref "J3") (pin "8") (pinfunction "8_8") (pintype "passive"))
      (node (ref "R3") (pin "8") (pinfunction "8_8") (pintype "passive"))
      (node (ref "S3") (pin "9") (pinfunction "9_9") (pintype "passive"))
    )
    (net (code "41") (name "TT4A") (class "Default")
      (node (ref "HEADSTAGE") (pin "33") (pinfunction "33_33") (pintype "bidirectional"))
      (node (ref "J2") (pin "1") (pinfunction "1_1") (pintype "passive"))
      (node (ref "R2") (pin "1") (pinfunction "1_1") (pintype "passive"))
      (node (ref "S2") (pin "16") (pinfunction "16_16") (pintype "passive"))
    )
    (net (code "42") (name "TT4B") (class "Default")
      (node (ref "HEADSTAGE") (pin "32") (pinfunction "32_32") (pintype "bidirectional"))
      (node (ref "J2") (pin "2") (pinfunction "2_2") (pintype "passive"))
      (node (ref "R2") (pin "2") (pinfunction "2_2") (pintype "passive"))
      (node (ref "S2") (pin "15") (pinfunction "15_15") (pintype "passive"))
    )
    (net (code "43") (name "TT4C") (class "Default")
      (node (ref "HEADSTAGE") (pin "31") (pinfunction "31_31") (pintype "bidirectional"))
      (node (ref "J2") (pin "3") (pinfunction "3_3") (pintype "passive"))
      (node (ref "R2") (pin "3") (pinfunction "3_3") (pintype "passive"))
      (node (ref "S2") (pin "14") (pinfunction "14_14") (pintype "passive"))
    )
    (net (code "44") (name "TT4D") (class "Default")
      (node (ref "HEADSTAGE") (pin "30") (pinfunction "30_30") (pintype "bidirectional"))
      (node (ref "J2") (pin "4") (pinfunction "4_4") (pintype "passive"))
      (node (ref "R2") (pin "4") (pinfunction "4_4") (pintype "passive"))
      (node (ref "S2") (pin "13") (pinfunction "13_13") (pintype "passive"))
    )
    (net (code "45") (name "TT5A") (class "Default")
      (node (ref "HEADSTAGE") (pin "29") (pinfunction "29_29") (pintype "bidirectional"))
      (node (ref "J2") (pin "5") (pinfunction "5_5") (pintype "passive"))
      (node (ref "R2") (pin "5") (pinfunction "5_5") (pintype "passive"))
      (node (ref "S2") (pin "12") (pinfunction "12_12") (pintype "passive"))
    )
    (net (code "46") (name "TT5B") (class "Default")
      (node (ref "HEADSTAGE") (pin "28") (pinfunction "28_28") (pintype "bidirectional"))
      (node (ref "J2") (pin "6") (pinfunction "6_6") (pintype "passive"))
      (node (ref "R2") (pin "6") (pinfunction "6_6") (pintype "passive"))
      (node (ref "S2") (pin "11") (pinfunction "11_11") (pintype "passive"))
    )
    (net (code "47") (name "TT5C") (class "Default")
      (node (ref "HEADSTAGE") (pin "27") (pinfunction "27_27") (pintype "bidirectional"))
      (node (ref "J2") (pin "7") (pinfunction "7_7") (pintype "passive"))
      (node (ref "R2") (pin "7") (pinfunction "7_7") (pintype "passive"))
      (node (ref "S2") (pin "10") (pinfunction "10_10") (pintype "passive"))
    )
    (net (code "48") (name "TT5D") (class "Default")
      (node (ref "HEADSTAGE") (pin "26") (pinfunction "26_26") (pintype "bidirectional"))
      (node (ref "J2") (pin "8") (pinfunction "8_8") (pintype "passive"))
      (node (ref "R2") (pin "8") (pinfunction "8_8") (pintype "passive"))
      (node (ref "S2") (pin "9") (pinfunction "9_9") (pintype "passive"))
    )
    (net (code "49") (name "TT6A") (class "Default")
      (node (ref "HEADSTAGE") (pin "25") (pinfunction "25_25") (pintype "bidirectional"))
      (node (ref "J1") (pin "1") (pinfunction "1_1") (pintype "passive"))
      (node (ref "R1") (pin "1") (pinfunction "1_1") (pintype "passive"))
      (node (ref "S1") (pin "16") (pinfunction "16_16") (pintype "passive"))
    )
    (net (code "50") (name "TT6B") (class "Default")
      (node (ref "HEADSTAGE") (pin "24") (pinfunction "24_24") (pintype "bidirectional"))
      (node (ref "J1") (pin "2") (pinfunction "2_2") (pintype "passive"))
      (node (ref "R1") (pin "2") (pinfunction "2_2") (pintype "passive"))
      (node (ref "S1") (pin "15") (pinfunction "15_15") (pintype "passive"))
    )
    (net (code "51") (name "TT6C") (class "Default")
      (node (ref "HEADSTAGE") (pin "23") (pinfunction "23_23") (pintype "bidirectional"))
      (node (ref "J1") (pin "3") (pinfunction "3_3") (pintype "passive"))
      (node (ref "R1") (pin "3") (pinfunction "3_3") (pintype "passive"))
      (node (ref "S1") (pin "14") (pinfunction "14_14") (pintype "passive"))
    )
    (net (code "52") (name "TT6D") (class "Default")
      (node (ref "HEADSTAGE") (pin "22") (pinfunction "22_22") (pintype "bidirectional"))
      (node (ref "J1") (pin "4") (pinfunction "4_4") (pintype "passive"))
      (node (ref "R1") (pin "4") (pinfunction "4_4") (pintype "passive"))
      (node (ref "S1") (pin "13") (pinfunction "13_13") (pintype "passive"))
    )
    (net (code "53") (name "TT7A") (class "Default")
      (node (ref "HEADSTAGE") (pin "21") (pinfunction "21_21") (pintype "bidirectional"))
      (node (ref "J1") (pin "5") (pinfunction "5_5") (pintype "passive"))
      (node (ref "R1") (pin "5") (pinfunction "5_5") (pintype "passive"))
      (node (ref "S1") (pin "12") (pinfunction "12_12") (pintype "passive"))
    )
    (net (code "54") (name "TT7B") (class "Default")
      (node (ref "HEADSTAGE") (pin "20") (pinfunction "20_20") (pintype "bidirectional"))
      (node (ref "J1") (pin "6") (pinfunction "6_6") (pintype "passive"))
      (node (ref "R1") (pin "6") (pinfunction "6_6") (pintype "passive"))
      (node (ref "S1") (pin "11") (pinfunction "11_11") (pintype "passive"))
    )
    (net (code "55") (name "TT7C") (class "Default")
      (node (ref "HEADSTAGE") (pin "19") (pinfunction "19_19") (pintype "bidirectional"))
      (node (ref "J1") (pin "7") (pinfunction "7_7") (pintype "passive"))
      (node (ref "R1") (pin "7") (pinfunction "7_7") (pintype "passive"))
      (node (ref "S1") (pin "10") (pinfunction "10_10") (pintype "passive"))
    )
    (net (code "56") (name "TT7D") (class "Default")
      (node (ref "HEADSTAGE") (pin "18") (pinfunction "18_18") (pintype "bidirectional"))
      (node (ref "J1") (pin "8") (pinfunction "8_8") (pintype "passive"))
      (node (ref "R1") (pin "8") (pinfunction "8_8") (pintype "passive"))
      (node (ref "S1") (pin "9") (pinfunction "9_9") (pintype "passive"))
    )
    (net (code "57") (name "TT8A") (class "Default")
      (node (ref "HEADSTAGE") (pin "17") (pinfunction "17_17") (pintype "bidirectional"))
      (node (ref "J5") (pin "1") (pinfunction "1_1") (pintype "passive"))
      (node (ref "R5") (pin "1") (pinfunction "1_1") (pintype "passive"))
      (node (ref "S5") (pin "16") (pinfunction "16_16") (pintype "passive"))
    )
    (net (code "58") (name "TT8B") (class "Default")
      (node (ref "HEADSTAGE") (pin "16") (pinfunction "16_16") (pintype "bidirectional"))
      (node (ref "J5") (pin "2") (pinfunction "2_2") (pintype "passive"))
      (node (ref "R5") (pin "2") (pinfunction "2_2") (pintype "passive"))
      (node (ref "S5") (pin "15") (pinfunction "15_15") (pintype "passive"))
    )
    (net (code "59") (name "TT8C") (class "Default")
      (node (ref "HEADSTAGE") (pin "15") (pinfunction "15_15") (pintype "bidirectional"))
      (node (ref "J5") (pin "3") (pinfunction "3_3") (pintype "passive"))
      (node (ref "R5") (pin "3") (pinfunction "3_3") (pintype "passive"))
      (node (ref "S5") (pin "14") (pinfunction "14_14") (pintype "passive"))
    )
    (net (code "60") (name "TT8D") (class "Default")
      (node (ref "HEADSTAGE") (pin "14") (pinfunction "14_14") (pintype "bidirectional"))
      (node (ref "J5") (pin "4") (pinfunction "4_4") (pintype "passive"))
      (node (ref "R5") (pin "4") (pinfunction "4_4") (pintype "passive"))
      (node (ref "S5") (pin "13") (pinfunction "13_13") (pintype "passive"))
    )
    (net (code "61") (name "TT9A") (class "Default")
      (node (ref "HEADSTAGE") (pin "13") (pinfunction "13_13") (pintype "bidirectional"))
      (node (ref "J5") (pin "5") (pinfunction "5_5") (pintype "passive"))
      (node (ref "R5") (pin "5") (pinfunction "5_5") (pintype "passive"))
      (node (ref "S5") (pin "12") (pinfunction "12_12") (pintype "passive"))
    )
    (net (code "62") (name "TT9B") (class "Default")
      (node (ref "HEADSTAGE") (pin "12") (pinfunction "12_12") (pintype "bidirectional"))
      (node (ref "J5") (pin "6") (pinfunction "6_6") (pintype "passive"))
      (node (ref "R5") (pin "6") (pinfunction "6_6") (pintype "passive"))
      (node (ref "S5") (pin "11") (pinfunction "11_11") (pintype "passive"))
    )
    (net (code "63") (name "TT9C") (class "Default")
      (node (ref "HEADSTAGE") (pin "11") (pinfunction "11_11") (pintype "bidirectional"))
      (node (ref "J5") (pin "7") (pinfunction "7_7") (pintype "passive"))
      (node (ref "R5") (pin "7") (pinfunction "7_7") (pintype "passive"))
      (node (ref "S5") (pin "10") (pinfunction "10_10") (pintype "passive"))
    )
    (net (code "64") (name "TT9D") (class "Default")
      (node (ref "HEADSTAGE") (pin "10") (pinfunction "10_10") (pintype "bidirectional"))
      (node (ref "J5") (pin "8") (pinfunction "8_8") (pintype "passive"))
      (node (ref "R5") (pin "8") (pinfunction "8_8") (pintype "passive"))
      (node (ref "S5") (pin "9") (pinfunction "9_9") (pintype "passive"))
    )
    (net (code "65") (name "TT10A") (class "Default")
      (node (ref "HEADSTAGE") (pin "9") (pinfunction "9_9") (pintype "bidirectional"))
      (node (ref "J6") (pin "1") (pinfunction "1_1") (pintype "passive"))
      (node (ref "R6") (pin "1") (pinfunction "1_1") (pintype "passive"))
      (node (ref "S6") (pin "16") (pinfunction "16_16") (pintype "passive"))
    )
    (net (code "66") (name "TT10B") (class "Default")
      (node (ref "HEADSTAGE") (pin "8") (pinfunction "8_8") (pintype "bidirectional"))
      (node (ref "J6") (pin "2") (pinfunction "2_2") (pintype "passive"))
      (node (ref "R6") (pin "2") (pinfunction "2_2") (pintype "passive"))
      (node (ref "S6") (pin "15") (pinfunction "15_15") (pintype "passive"))
    )
    (net (code "67") (name "TT10C") (class "Default")
      (node (ref "HEADSTAGE") (pin "7") (pinfunction "7_7") (pintype "bidirectional"))
      (node (ref "J6") (pin "3") (pinfunction "3_3") (pintype "passive"))
      (node (ref "R6") (pin "3") (pinfunction "3_3") (pintype "passive"))
      (node (ref "S6") (pin "14") (pinfunction "14_14") (pintype "passive"))
    )
    (net (code "68") (name "TT10D") (class "Default")
      (node (ref "HEADSTAGE") (pin "6") (pinfunction "6_6") (pintype "bidirectional"))
      (node (ref "J6") (pin "4") (pinfunction "4_4") (pintype "passive"))
      (node (ref "R6") (pin "4") (pinfunction "4_4") (pintype "passive"))
      (node (ref "S6") (pin "13") (pinfunction "13_13") (pintype "passive"))
    )
    (net (code "69") (name "TT11A") (class "Default")
      (node (ref "HEADSTAGE") (pin "5") (pinfunction "5_5") (pintype "bidirectional"))
      (node (ref "J6") (pin "5") (pinfunction "5_5") (pintype "passive"))
      (node (ref "R6") (pin "5") (pinfunction "5_5") (pintype "passive"))
      (node (ref "S6") (pin "12") (pinfunction "12_12") (pintype "passive"))
    )
    (net (code "70") (name "TT11B") (class "Default")
      (node (ref "HEADSTAGE") (pin "4") (pinfunction "4_4") (pintype "bidirectional"))
      (node (ref "J6") (pin "6") (pinfunction "6_6") (pintype "passive"))
      (node (ref "R6") (pin "6") (pinfunction "6_6") (pintype "passive"))
      (node (ref "S6") (pin "11") (pinfunction "11_11") (pintype "passive"))
    )
    (net (code "71") (name "TT11C") (class "Default")
      (node (ref "HEADSTAGE") (pin "3") (pinfunction "3_3") (pintype "bidirectional"))
      (node (ref "J6") (pin "7") (pinfunction "7_7") (pintype "passive"))
      (node (ref "R6") (pin "7") (pinfunction "7_7") (pintype "passive"))
      (node (ref "S6") (pin "10") (pinfunction "10_10") (pintype "passive"))
    )
    (net (code "72") (name "TT11D") (class "Default")
      (node (ref "HEADSTAGE") (pin "2") (pinfunction "2_2") (pintype "bidirectional"))
      (node (ref "J6") (pin "8") (pinfunction "8_8") (pintype "passive"))
      (node (ref "R6") (pin "8") (pinfunction "8_8") (pintype "passive"))
      (node (ref "S6") (pin "9") (pinfunction "9_9") (pintype "passive"))
    )
    (net (code "73") (name "TT12A") (class "Default")
      (node (ref "HEADSTAGE") (pin "69") (pinfunction "69_69") (pintype "bidirectional"))
      (node (ref "J7") (pin "1") (pinfunction "1_1") (pintype "passive"))
      (node (ref "R7") (pin "1") (pinfunction "1_1") (pintype "passive"))
      (node (ref "S7") (pin "16") (pinfunction "16_16") (pintype "passive"))
    )
    (net (code "74") (name "TT12B") (class "Default")
      (node (ref "HEADSTAGE") (pin "68") (pinfunction "68_68") (pintype "bidirectional"))
      (node (ref "J7") (pin "2") (pinfunction "2_2") (pintype "passive"))
      (node (ref "R7") (pin "2") (pinfunction "2_2") (pintype "passive"))
      (node (ref "S7") (pin "15") (pinfunction "15_15") (pintype "passive"))
    )
    (net (code "75") (name "TT12C") (class "Default")
      (node (ref "HEADSTAGE") (pin "67") (pinfunction "67_67") (pintype "bidirectional"))
      (node (ref "J7") (pin "3") (pinfunction "3_3") (pintype "passive"))
      (node (ref "R7") (pin "3") (pinfunction "3_3") (pintype "passive"))
      (node (ref "S7") (pin "14") (pinfunction "14_14") (pintype "passive"))
    )
    (net (code "76") (name "TT12D") (class "Default")
      (node (ref "HEADSTAGE") (pin "66") (pinfunction "66_66") (pintype "bidirectional"))
      (node (ref "J7") (pin "4") (pinfunction "4_4") (pintype "passive"))
      (node (ref "R7") (pin "4") (pinfunction "4_4") (pintype "passive"))
      (node (ref "S7") (pin "13") (pinfunction "13_13") (pintype "passive"))
    )
    (net (code "77") (name "TT13A") (class "Default")
      (node (ref "HEADSTAGE") (pin "65") (pinfunction "65_65") (pintype "bidirectional"))
      (node (ref "J7") (pin "5") (pinfunction "5_5") (pintype "passive"))
      (node (ref "R7") (pin "5") (pinfunction "5_5") (pintype "passive"))
      (node (ref "S7") (pin "12") (pinfunction "12_12") (pintype "passive"))
    )
    (net (code "78") (name "TT13B") (class "Default")
      (node (ref "HEADSTAGE") (pin "64") (pinfunction "64_64") (pintype "bidirectional"))
      (node (ref "J7") (pin "6") (pinfunction "6_6") (pintype "passive"))
      (node (ref "R7") (pin "6") (pinfunction "6_6") (pintype "passive"))
      (node (ref "S7") (pin "11") (pinfunction "11_11") (pintype "passive"))
    )
    (net (code "79") (name "TT13C") (class "Default")
      (node (ref "HEADSTAGE") (pin "63") (pinfunction "63_63") (pintype "bidirectional"))
      (node (ref "J7") (pin "7") (pinfunction "7_7") (pintype "passive"))
      (node (ref "R7") (pin "7") (pinfunction "7_7") (pintype "passive"))
      (node (ref "S7") (pin "10") (pinfunction "10_10") (pintype "passive"))
    )
    (net (code "80") (name "TT13D") (class "Default")
      (node (ref "HEADSTAGE") (pin "62") (pinfunction "62_62") (pintype "bidirectional"))
      (node (ref "J7") (pin "8") (pinfunction "8_8") (pintype "passive"))
      (node (ref "R7") (pin "8") (pinfunction "8_8") (pintype "passive"))
      (node (ref "S7") (pin "9") (pinfunction "9_9") (pintype "passive"))
    )
    (net (code "81") (name "TT14A") (class "Default")
      (node (ref "HEADSTAGE") (pin "61") (pinfunction "61_61") (pintype "bidirectional"))
      (node (ref "J8") (pin "1") (pinfunction "1_1") (pintype "passive"))
      (node (ref "R8") (pin "1") (pinfunction "1_1") (pintype "passive"))
      (node (ref "S8") (pin "16") (pinfunction "16_16") (pintype "passive"))
    )
    (net (code "82") (name "TT14B") (class "Default")
      (node (ref "HEADSTAGE") (pin "60") (pinfunction "60_60") (pintype "bidirectional"))
      (node (ref "J8") (pin "2") (pinfunction "2_2") (pintype "passive"))
      (node (ref "R8") (pin "2") (pinfunction "2_2") (pintype "passive"))
      (node (ref "S8") (pin "15") (pinfunction "15_15") (pintype "passive"))
    )
    (net (code "83") (name "TT14C") (class "Default")
      (node (ref "HEADSTAGE") (pin "59") (pinfunction "59_59") (pintype "bidirectional"))
      (node (ref "J8") (pin "3") (pinfunction "3_3") (pintype "passive"))
      (node (ref "R8") (pin "3") (pinfunction "3_3") (pintype "passive"))
      (node (ref "S8") (pin "14") (pinfunction "14_14") (pintype "passive"))
    )
    (net (code "84") (name "TT14D") (class "Default")
      (node (ref "HEADSTAGE") (pin "58") (pinfunction "58_58") (pintype "bidirectional"))
      (node (ref "J8") (pin "4") (pinfunction "4_4") (pintype "passive"))
      (node (ref "R8") (pin "4") (pinfunction "4_4") (pintype "passive"))
      (node (ref "S8") (pin "13") (pinfunction "13_13") (pintype "passive"))
    )
    (net (code "85") (name "TT15A") (class "Default")
      (node (ref "HEADSTAGE") (pin "57") (pinfunction "57_57") (pintype "bidirectional"))
      (node (ref "J8") (pin "5") (pinfunction "5_5") (pintype "passive"))
      (node (ref "R8") (pin "5") (pinfunction "5_5") (pintype "passive"))
      (node (ref "S8") (pin "12") (pinfunction "12_12") (pintype "passive"))
    )
    (net (code "86") (name "TT15B") (class "Default")
      (node (ref "HEADSTAGE") (pin "56") (pinfunction "56_56") (pintype "bidirectional"))
      (node (ref "J8") (pin "6") (pinfunction "6_6") (pintype "passive"))
      (node (ref "R8") (pin "6") (pinfunction "6_6") (pintype "passive"))
      (node (ref "S8") (pin "11") (pinfunction "11_11") (pintype "passive"))
    )
    (net (code "87") (name "TT15C") (class "Default")
      (node (ref "HEADSTAGE") (pin "55") (pinfunction "55_55") (pintype "bidirectional"))
      (node (ref "J8") (pin "7") (pinfunction "7_7") (pintype "passive"))
      (node (ref "R8") (pin "7") (pinfunction "7_7") (pintype "passive"))
      (node (ref "S8") (pin "10") (pinfunction "10_10") (pintype "passive"))
    )
    (net (code "88") (name "TT15D") (class "Default")
      (node (ref "HEADSTAGE") (pin "54") (pinfunction "54_54") (pintype "bidirectional"))
      (node (ref "J8") (pin "8") (pinfunction "8_8") (pintype "passive"))
      (node (ref "R8") (pin "8") (pinfunction "8_8") (pintype "passive"))
      (node (ref "S8") (pin "9") (pinfunction "9_9") (pintype "passive"))
    )
  )
)
